# untitled.net
KiCad netlist of a schematic drawn in EAGLE
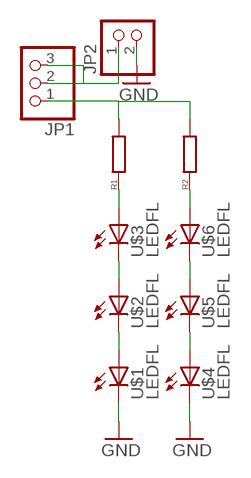
[diagram p0: schematic, sheet 1]

(export (version "E")
  (design (tool "Eeschema 10.0.6"))
  (components
    (comp (ref "JP1")
      (value "PINHD-1X03_2.54-SMD-90°")
      (footprint "eagle-import:1X03SMD_90")
      (libsource (lib "eagle-import") (part "PINHD-1X03_2.54-SMD-90°"))
    )
    (comp (ref "JP2")
      (value "PINHD-1X02_2.54-SMD-90°")
      (footprint "eagle-import:1X02SMD_90")
      (libsource (lib "eagle-import") (part "PINHD-1X02_2.54-SMD-90°"))
    )
    (comp (ref "R1")
      (value "R0805")
      (footprint "eagle-import:R0805")
      (libsource (lib "eagle-import") (part "R0805"))
    )
    (comp (ref "R2")
      (value "R0805")
      (footprint "eagle-import:R0805")
      (libsource (lib "eagle-import") (part "R0805"))
    )
    (comp (ref "U$1")
      (value "LEDFL")
      (footprint "eagle-import:LED1")
      (libsource (lib "eagle-import") (part "LEDFL"))
    )
    (comp (ref "U$2")
      (value "LEDFL")
      (footprint "eagle-import:LED1")
      (libsource (lib "eagle-import") (part "LEDFL"))
    )
    (comp (ref "U$3")
      (value "LEDFL")
      (footprint "eagle-import:LED1")
      (libsource (lib "eagle-import") (part "LEDFL"))
    )
    (comp (ref "U$4")
      (value "LEDFL")
      (footprint "eagle-import:LED1")
      (libsource (lib "eagle-import") (part "LEDFL"))
    )
    (comp (ref "U$5")
      (value "LEDFL")
      (footprint "eagle-import:LED1")
      (libsource (lib "eagle-import") (part "LEDFL"))
    )
    (comp (ref "U$6")
      (value "LEDFL")
      (footprint "eagle-import:LED1")
      (libsource (lib "eagle-import") (part "LEDFL"))
    )
  )
  (nets
    (net (code "1") (name "GND") (class "Default")
      (node (ref "JP2") (pin "2") (pinfunction "2_2") (pintype "passive"))
      (node (ref "U$1") (pin "P$2") (pinfunction "C_P$2") (pintype "passive"))
      (node (ref "U$4") (pin "P$2") (pinfunction "C_P$2") (pintype "passive"))
    )
    (net (code "2") (name "Net-(JP1-Pad1)") (class "Default")
      (node (ref "JP1") (pin "1") (pinfunction "1_1") (pintype "passive"))
      (node (ref "R1") (pin "2") (pinfunction "2_2") (pintype "passive"))
      (node (ref "R2") (pin "2") (pinfunction "2_2") (pintype "passive"))
    )
    (net (code "3") (name "Net-(JP1-Pad2)") (class "Default")
      (node (ref "JP1") (pin "2") (pinfunction "2_2") (pintype "passive"))
      (node (ref "JP1") (pin "3") (pinfunction "3_3") (pintype "passive"))
      (node (ref "JP2") (pin "1") (pinfunction "1_1") (pintype "passive"))
    )
    (net (code "4") (name "Net-(U$1-A)") (class "Default")
      (node (ref "U$1") (pin "P$1") (pinfunction "A_P$1") (pintype "passive"))
      (node (ref "U$2") (pin "P$2") (pinfunction "C_P$2") (pintype "passive"))
    )
    (net (code "5") (name "Net-(U$2-A)") (class "Default")
      (node (ref "U$2") (pin "P$1") (pinfunction "A_P$1") (pintype "passive"))
      (node (ref "U$3") (pin "P$2") (pinfunction "C_P$2") (pintype "passive"))
    )
    (net (code "6") (name "Net-(U$3-A)") (class "Default")
      (node (ref "R1") (pin "1") (pinfunction "1_1") (pintype "passive"))
      (node (ref "U$3") (pin "P$1") (pinfunction "A_P$1") (pintype "passive"))
    )
    (net (code "7") (name "Net-(U$4-A)") (class "Default")
      (node (ref "U$4") (pin "P$1") (pinfunction "A_P$1") (pintype "passive"))
      (node (ref "U$5") (pin "P$2") (pinfunction "C_P$2") (pintype "passive"))
    )
    (net (code "8") (name "Net-(U$5-A)") (class "Default")
      (node (ref "U$5") (pin "P$1") (pinfunction "A_P$1") (pintype "passive"))
      (node (ref "U$6") (pin "P$2") (pinfunction "C_P$2") (pintype "passive"))
    )
    (net (code "9") (name "Net-(U$6-A)") (class "Default")
      (node (ref "R2") (pin "1") (pinfunction "1_1") (pintype "passive"))
      (node (ref "U$6") (pin "P$1") (pinfunction "A_P$1") (pintype "passive"))
    )
  )
)
